# Esquematico.net
KiCad netlist of a schematic drawn in EAGLE
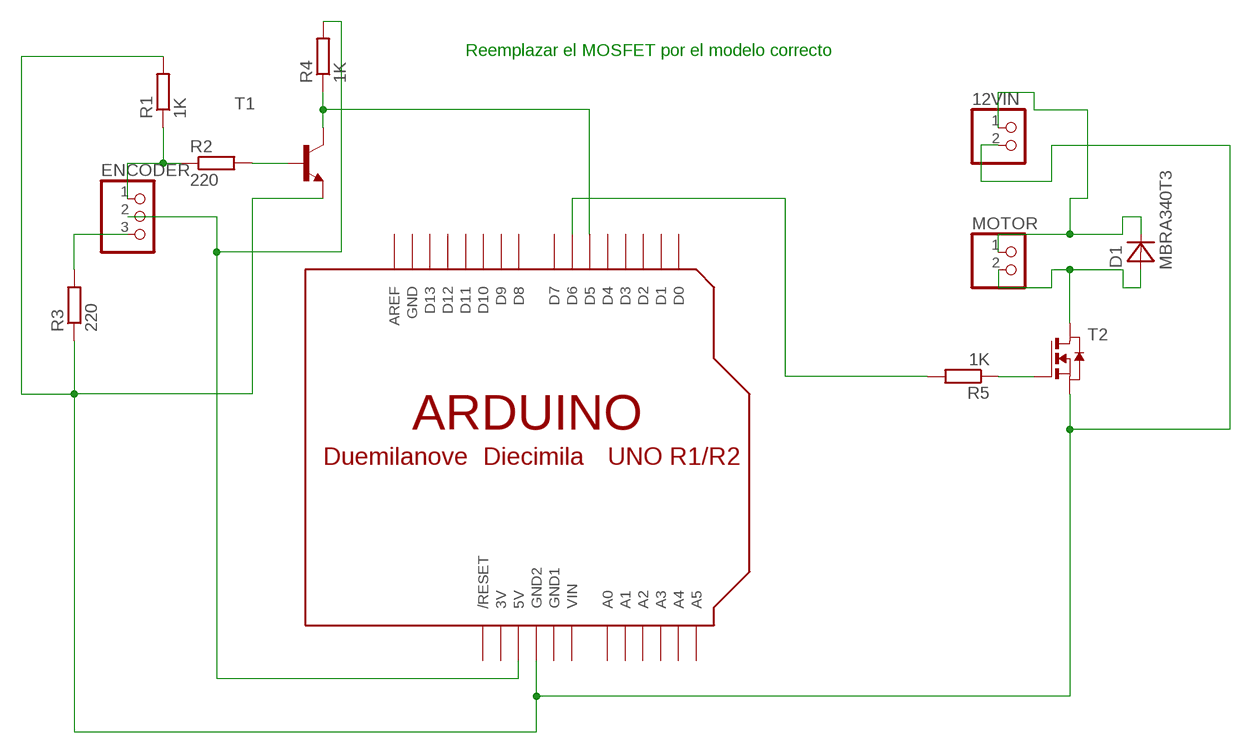
[diagram p0: schematic, sheet 1]

(export (version "E")
  (design (tool "Eeschema 10.0.6"))
  (components
    (comp (ref "12VIN")
      (value "PINHD-1X2")
      (footprint "eagle-import:1X02")
      (libsource (lib "eagle-import") (part "PINHD-1X2"))
    )
    (comp (ref "D1")
      (value "MBRA340T3")
      (footprint "eagle-import:SMA")
      (libsource (lib "eagle-import") (part "MBRA340T3"))
    )
    (comp (ref "ENCODER")
      (value "PINHD-1X3CB")
      (footprint "eagle-import:1X03-CLEANBIG")
      (libsource (lib "eagle-import") (part "PINHD-1X3CB"))
    )
    (comp (ref "MOTOR")
      (value "PINHD-1X2")
      (footprint "eagle-import:1X02")
      (libsource (lib "eagle-import") (part "PINHD-1X2"))
    )
    (comp (ref "R1")
      (value "1K")
      (footprint "eagle-import:R1206")
      (libsource (lib "eagle-import") (part "R-EU_R1206"))
    )
    (comp (ref "R2")
      (value "220")
      (footprint "eagle-import:R1206")
      (libsource (lib "eagle-import") (part "R-EU_R1206"))
    )
    (comp (ref "R3")
      (value "220")
      (footprint "eagle-import:R1206")
      (libsource (lib "eagle-import") (part "R-EU_R1206"))
    )
    (comp (ref "R4")
      (value "1K")
      (footprint "eagle-import:R1206")
      (libsource (lib "eagle-import") (part "R-EU_R1206"))
    )
    (comp (ref "R5")
      (value "1K")
      (footprint "eagle-import:R1206")
      (libsource (lib "eagle-import") (part "R-EU_R1206"))
    )
    (comp (ref "T1")
      (value "BC817-40LT1-NPN-SOT23-BEC")
      (footprint "eagle-import:SOT23-BEC")
      (libsource (lib "eagle-import") (part "-NPN-SOT23-BECBC817-40LT1"))
    )
    (comp (ref "T2")
      (value "NMOSSOT223")
      (footprint "eagle-import:SOT223")
      (libsource (lib "eagle-import") (part "NMOSSOT223"))
    )
    (comp (ref "U$1")
      (value "ARDUINO-NOHOLE")
      (footprint "eagle-import:ARDUINO-NOHOLE")
      (libsource (lib "eagle-import") (part "ARDUINO-NOHOLE"))
    )
  )
  (nets
    (net (code "1") (name "/3V") (class "Default")
      (node (ref "U$1") (pin "3V") (pinfunction "3V_3V") (pintype "power_in"))
    )
    (net (code "2") (name "/GND") (class "Default")
      (node (ref "U$1") (pin "GND") (pinfunction "GND_GND") (pintype "power_in"))
    )
    (net (code "3") (name "/GND1") (class "Default")
      (node (ref "U$1") (pin "GND1") (pinfunction "GND1_GND1") (pintype "power_in"))
    )
    (net (code "4") (name "/VIN") (class "Default")
      (node (ref "U$1") (pin "VIN") (pinfunction "VIN_VIN") (pintype "power_in"))
    )
    (net (code "5") (name "Net-(12VIN-Pad1)") (class "Default")
      (node (ref "12VIN") (pin "1") (pinfunction "1_1") (pintype "passive"))
      (node (ref "D1") (pin "C") (pinfunction "C_C") (pintype "passive"))
      (node (ref "MOTOR") (pin "1") (pinfunction "1_1") (pintype "passive"))
    )
    (net (code "6") (name "Net-(D1-PadA)") (class "Default")
      (node (ref "D1") (pin "A") (pinfunction "A_A") (pintype "passive"))
      (node (ref "MOTOR") (pin "2") (pinfunction "2_2") (pintype "passive"))
      (node (ref "T2") (pin "2") (pinfunction "D_2") (pintype "passive"))
      (node (ref "T2") (pin "4") (pinfunction "D_4") (pintype "passive"))
    )
    (net (code "7") (name "Net-(ENCODER-Pad1)") (class "Default")
      (node (ref "ENCODER") (pin "1") (pinfunction "1_1") (pintype "passive"))
      (node (ref "R1") (pin "1") (pinfunction "1_1") (pintype "passive"))
      (node (ref "R2") (pin "1") (pinfunction "1_1") (pintype "passive"))
    )
    (net (code "8") (name "Net-(ENCODER-Pad2)") (class "Default")
      (node (ref "ENCODER") (pin "2") (pinfunction "2_2") (pintype "passive"))
      (node (ref "R4") (pin "2") (pinfunction "2_2") (pintype "passive"))
      (node (ref "U$1") (pin "5V") (pinfunction "5V_5V") (pintype "power_in"))
    )
    (net (code "9") (name "Net-(ENCODER-Pad3)") (class "Default")
      (node (ref "ENCODER") (pin "3") (pinfunction "3_3") (pintype "passive"))
      (node (ref "R3") (pin "2") (pinfunction "2_2") (pintype "passive"))
    )
    (net (code "10") (name "Net-(R2-Pad2)") (class "Default")
      (node (ref "R2") (pin "2") (pinfunction "2_2") (pintype "passive"))
      (node (ref "T1") (pin "B") (pinfunction "B_B") (pintype "passive"))
    )
    (net (code "11") (name "Net-(R4-Pad1)") (class "Default")
      (node (ref "R4") (pin "1") (pinfunction "1_1") (pintype "passive"))
      (node (ref "T1") (pin "C") (pinfunction "C_C") (pintype "passive"))
      (node (ref "U$1") (pin "D5") (pinfunction "D5_D5") (pintype "bidirectional"))
    )
    (net (code "12") (name "Net-(R5-Pad2)") (class "Default")
      (node (ref "R5") (pin "2") (pinfunction "2_2") (pintype "passive"))
      (node (ref "U$1") (pin "D6") (pinfunction "D6_D6") (pintype "bidirectional"))
    )
    (net (code "13") (name "Net-(T2-G)") (class "Default")
      (node (ref "R5") (pin "1") (pinfunction "1_1") (pintype "passive"))
      (node (ref "T2") (pin "1") (pinfunction "G_1") (pintype "passive"))
    )
    (net (code "14") (name "Net-(T2-S)") (class "Default")
      (node (ref "12VIN") (pin "2") (pinfunction "2_2") (pintype "passive"))
      (node (ref "R1") (pin "2") (pinfunction "2_2") (pintype "passive"))
      (node (ref "R3") (pin "1") (pinfunction "1_1") (pintype "passive"))
      (node (ref "T1") (pin "E") (pinfunction "E_E") (pintype "passive"))
      (node (ref "T2") (pin "3") (pinfunction "S_3") (pintype "passive"))
      (node (ref "U$1") (pin "GND2") (pinfunction "GND2_GND2") (pintype "power_in"))
    )
    (net (code "15") (name "unconnected-(U$1-PadA0)") (class "Default")
      (node (ref "U$1") (pin "A0") (pinfunction "A0_A0") (pintype "bidirectional"))
    )
    (net (code "16") (name "unconnected-(U$1-PadA1)") (class "Default")
      (node (ref "U$1") (pin "A1") (pinfunction "A1_A1") (pintype "bidirectional"))
    )
    (net (code "17") (name "unconnected-(U$1-PadA2)") (class "Default")
      (node (ref "U$1") (pin "A2") (pinfunction "A2_A2") (pintype "bidirectional"))
    )
    (net (code "18") (name "unconnected-(U$1-PadA3)") (class "Default")
      (node (ref "U$1") (pin "A3") (pinfunction "A3_A3") (pintype "bidirectional"))
    )
    (net (code "19") (name "unconnected-(U$1-PadA4)") (class "Default")
      (node (ref "U$1") (pin "A4") (pinfunction "A4_A4") (pintype "bidirectional"))
    )
    (net (code "20") (name "unconnected-(U$1-PadA5)") (class "Default")
      (node (ref "U$1") (pin "A5") (pinfunction "A5_A5") (pintype "bidirectional"))
    )
    (net (code "21") (name "unconnected-(U$1-PadAREF)") (class "Default")
      (node (ref "U$1") (pin "AREF") (pinfunction "AREF_AREF") (pintype "bidirectional"))
    )
    (net (code "22") (name "unconnected-(U$1-PadD0)") (class "Default")
      (node (ref "U$1") (pin "D0") (pinfunction "D0_D0") (pintype "bidirectional"))
    )
    (net (code "23") (name "unconnected-(U$1-PadD1)") (class "Default")
      (node (ref "U$1") (pin "D1") (pinfunction "D1_D1") (pintype "bidirectional"))
    )
    (net (code "24") (name "unconnected-(U$1-PadD2)") (class "Default")
      (node (ref "U$1") (pin "D2") (pinfunction "D2_D2") (pintype "bidirectional"))
    )
    (net (code "25") (name "unconnected-(U$1-PadD3)") (class "Default")
      (node (ref "U$1") (pin "D3") (pinfunction "D3_D3") (pintype "bidirectional"))
    )
    (net (code "26") (name "unconnected-(U$1-PadD4)") (class "Default")
      (node (ref "U$1") (pin "D4") (pinfunction "D4_D4") (pintype "bidirectional"))
    )
    (net (code "27") (name "unconnected-(U$1-PadD7)") (class "Default")
      (node (ref "U$1") (pin "D7") (pinfunction "D7_D7") (pintype "bidirectional"))
    )
    (net (code "28") (name "unconnected-(U$1-PadD8)") (class "Default")
      (node (ref "U$1") (pin "D8") (pinfunction "D8_D8") (pintype "bidirectional"))
    )
    (net (code "29") (name "unconnected-(U$1-PadD9)") (class "Default")
      (node (ref "U$1") (pin "D9") (pinfunction "D9_D9") (pintype "bidirectional"))
    )
    (net (code "30") (name "unconnected-(U$1-PadD10)") (class "Default")
      (node (ref "U$1") (pin "D10") (pinfunction "D10_D10") (pintype "bidirectional"))
    )
    (net (code "31") (name "unconnected-(U$1-PadD11)") (class "Default")
      (node (ref "U$1") (pin "D11") (pinfunction "D11_D11") (pintype "bidirectional"))
    )
    (net (code "32") (name "unconnected-(U$1-PadD12)") (class "Default")
      (node (ref "U$1") (pin "D12") (pinfunction "D12_D12") (pintype "bidirectional"))
    )
    (net (code "33") (name "unconnected-(U$1-PadD13)") (class "Default")
      (node (ref "U$1") (pin "D13") (pinfunction "D13_D13") (pintype "bidirectional"))
    )
    (net (code "34") (name "unconnected-(U$1-{slash}RESET-PadRESET)") (class "Default")
      (node (ref "U$1") (pin "RESET") (pinfunction "/RESET_RESET") (pintype "bidirectional"))
    )
  )
)
